# GD_Tcontroller_Power.net
KiCad netlist of a schematic drawn in Altium Designer
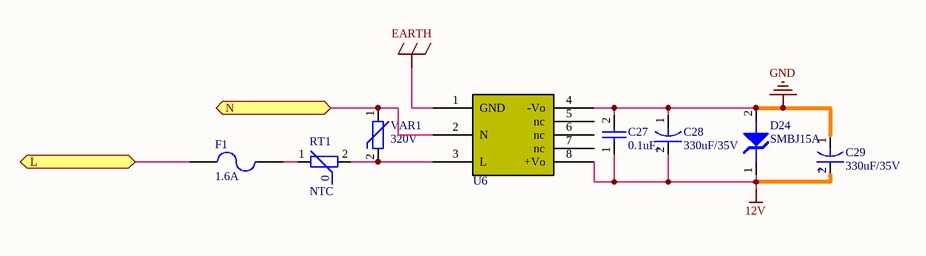
[diagram p0: GD_Tcontroller_Power.SchDoc]

(export (version "E")
  (design (tool "Eeschema 10.0.6"))
  (components
    (comp (ref "C27")
      (value "0.1uF")
      (footprint "C0805")
      (description "CAP SMD CR X7R 50V 10% 0.1uF 0805 ROHS")
      (fields (field (name "MANUFACTURER") "YAGEO") (field (name "Comment") "CAP"))
      (libsource (lib "enlogic") (part "CAP"))
    )
    (comp (ref "C28")
      (value "330uF/35V")
      (footprint "CA10X16P5")
      (description "CAP 35V 20% 330uF 10X16X0.6MM ROHS，7000hours")
      (fields (field (name "MANUFACTURER") "NIPPON CHEMI-CON") (field (name "Comment") "CAPACITOR"))
      (libsource (lib "Enlogic") (part "CAPACITOR"))
    )
    (comp (ref "C29")
      (value "330uF/35V")
      (footprint "CA10X16P5")
      (description "CAP 35V 20% 330uF 10X16X0.6MM ROHS，7000hours")
      (fields (field (name "MANUFACTURER") "NIPPON CHEMI-CON") (field (name "Comment") "CAPACITOR"))
      (libsource (lib "Enlogic") (part "CAPACITOR"))
    )
    (comp (ref "D24")
      (value "SMBJ15A")
      (footprint "SMB")
      (fields (field (name "MANUFACTURER") "Bourns"))
      (libsource (lib "Enlogic") (part "ZENER"))
    )
    (comp (ref "F1")
      (value "1.6A")
      (footprint "392XXXX000")
      (description "FUSE,Ceramic,1.6A,25A@250VAC,8.5x8mm,ROHS")
      (fields (field (name "MANUFACTURER") "LITTELFUSE") (field (name "Comment") "Fuse"))
      (libsource (lib "Enlogic") (part "Fuse"))
    )
    (comp (ref "RT1")
      (value "NTC")
      (footprint "NTC8_5x6P5")
      (fields (field (name "MANUFACTURER") "SEMITEC"))
      (libsource (lib "Enlogic") (part "NTC"))
    )
    (comp (ref "U6")
      (value "LH05-10B12")
      (footprint "LH05X")
      (fields (field (name "MANUFACTURER") "Mornsun"))
      (libsource (lib "Schlib1") (part "LH05-10B05"))
    )
    (comp (ref "VAR1")
      (value "320V")
      (footprint "VAR16_7X6_6P7_5")
      (description "MOV 320V 14MM 80J LDFR ROHS")
      (fields (field (name "MANUFACTURER") "LITTELFUSE") (field (name "Comment") "VARISTOR"))
      (libsource (lib "Enlogic") (part "VARISTOR"))
    )
  )
  (nets
    (net (code "1") (name "/L") (class "Default")
      (node (ref "F1") (pin "1") (pinfunction "1_1") (pintype "passive"))
    )
    (net (code "2") (name "/N") (class "Default")
      (node (ref "U6") (pin "2") (pinfunction "N_2") (pintype "passive"))
      (node (ref "VAR1") (pin "1") (pinfunction "1_1") (pintype "passive"))
    )
    (net (code "3") (name "12V") (class "Default")
      (node (ref "C27") (pin "1") (pinfunction "1_1") (pintype "passive"))
      (node (ref "C28") (pin "2") (pinfunction "2_2") (pintype "passive"))
      (node (ref "C29") (pin "2") (pinfunction "2_2") (pintype "passive"))
      (node (ref "D24") (pin "1") (pintype "passive"))
      (node (ref "U6") (pin "8") (pinfunction "+Vo_8") (pintype "passive"))
    )
    (net (code "4") (name "EARTH") (class "Default")
      (node (ref "U6") (pin "1") (pinfunction "GND_1") (pintype "passive"))
    )
    (net (code "5") (name "GND") (class "Default")
      (node (ref "C27") (pin "2") (pinfunction "2_2") (pintype "passive"))
      (node (ref "C28") (pin "1") (pinfunction "1_1") (pintype "passive"))
      (node (ref "C29") (pin "1") (pinfunction "1_1") (pintype "passive"))
      (node (ref "D24") (pin "2") (pintype "passive"))
      (node (ref "U6") (pin "4") (pinfunction "-Vo_4") (pintype "passive"))
    )
    (net (code "6") (name "Net-(F1-Pad2)") (class "Default")
      (node (ref "F1") (pin "2") (pinfunction "2_2") (pintype "passive"))
      (node (ref "RT1") (pin "1") (pinfunction "1_1") (pintype "passive"))
    )
    (net (code "7") (name "Net-(U6-L)") (class "Default")
      (node (ref "RT1") (pin "2") (pinfunction "2_2") (pintype "passive"))
      (node (ref "U6") (pin "3") (pinfunction "L_3") (pintype "passive"))
      (node (ref "VAR1") (pin "2") (pinfunction "2_2") (pintype "passive"))
    )
    (net (code "8") (name "unconnected-(U6-nc-Pad5)") (class "Default")
      (node (ref "U6") (pin "5") (pinfunction "nc_5") (pintype "passive"))
    )
    (net (code "9") (name "unconnected-(U6-nc-Pad6)") (class "Default")
      (node (ref "U6") (pin "6") (pinfunction "nc_6") (pintype "passive"))
    )
    (net (code "10") (name "unconnected-(U6-nc-Pad7)") (class "Default")
      (node (ref "U6") (pin "7") (pinfunction "nc_7") (pintype "passive"))
    )
  )
)
